# 1-Schematic_optical-sensor.net
KiCad netlist of a schematic drawn in EasyEDA
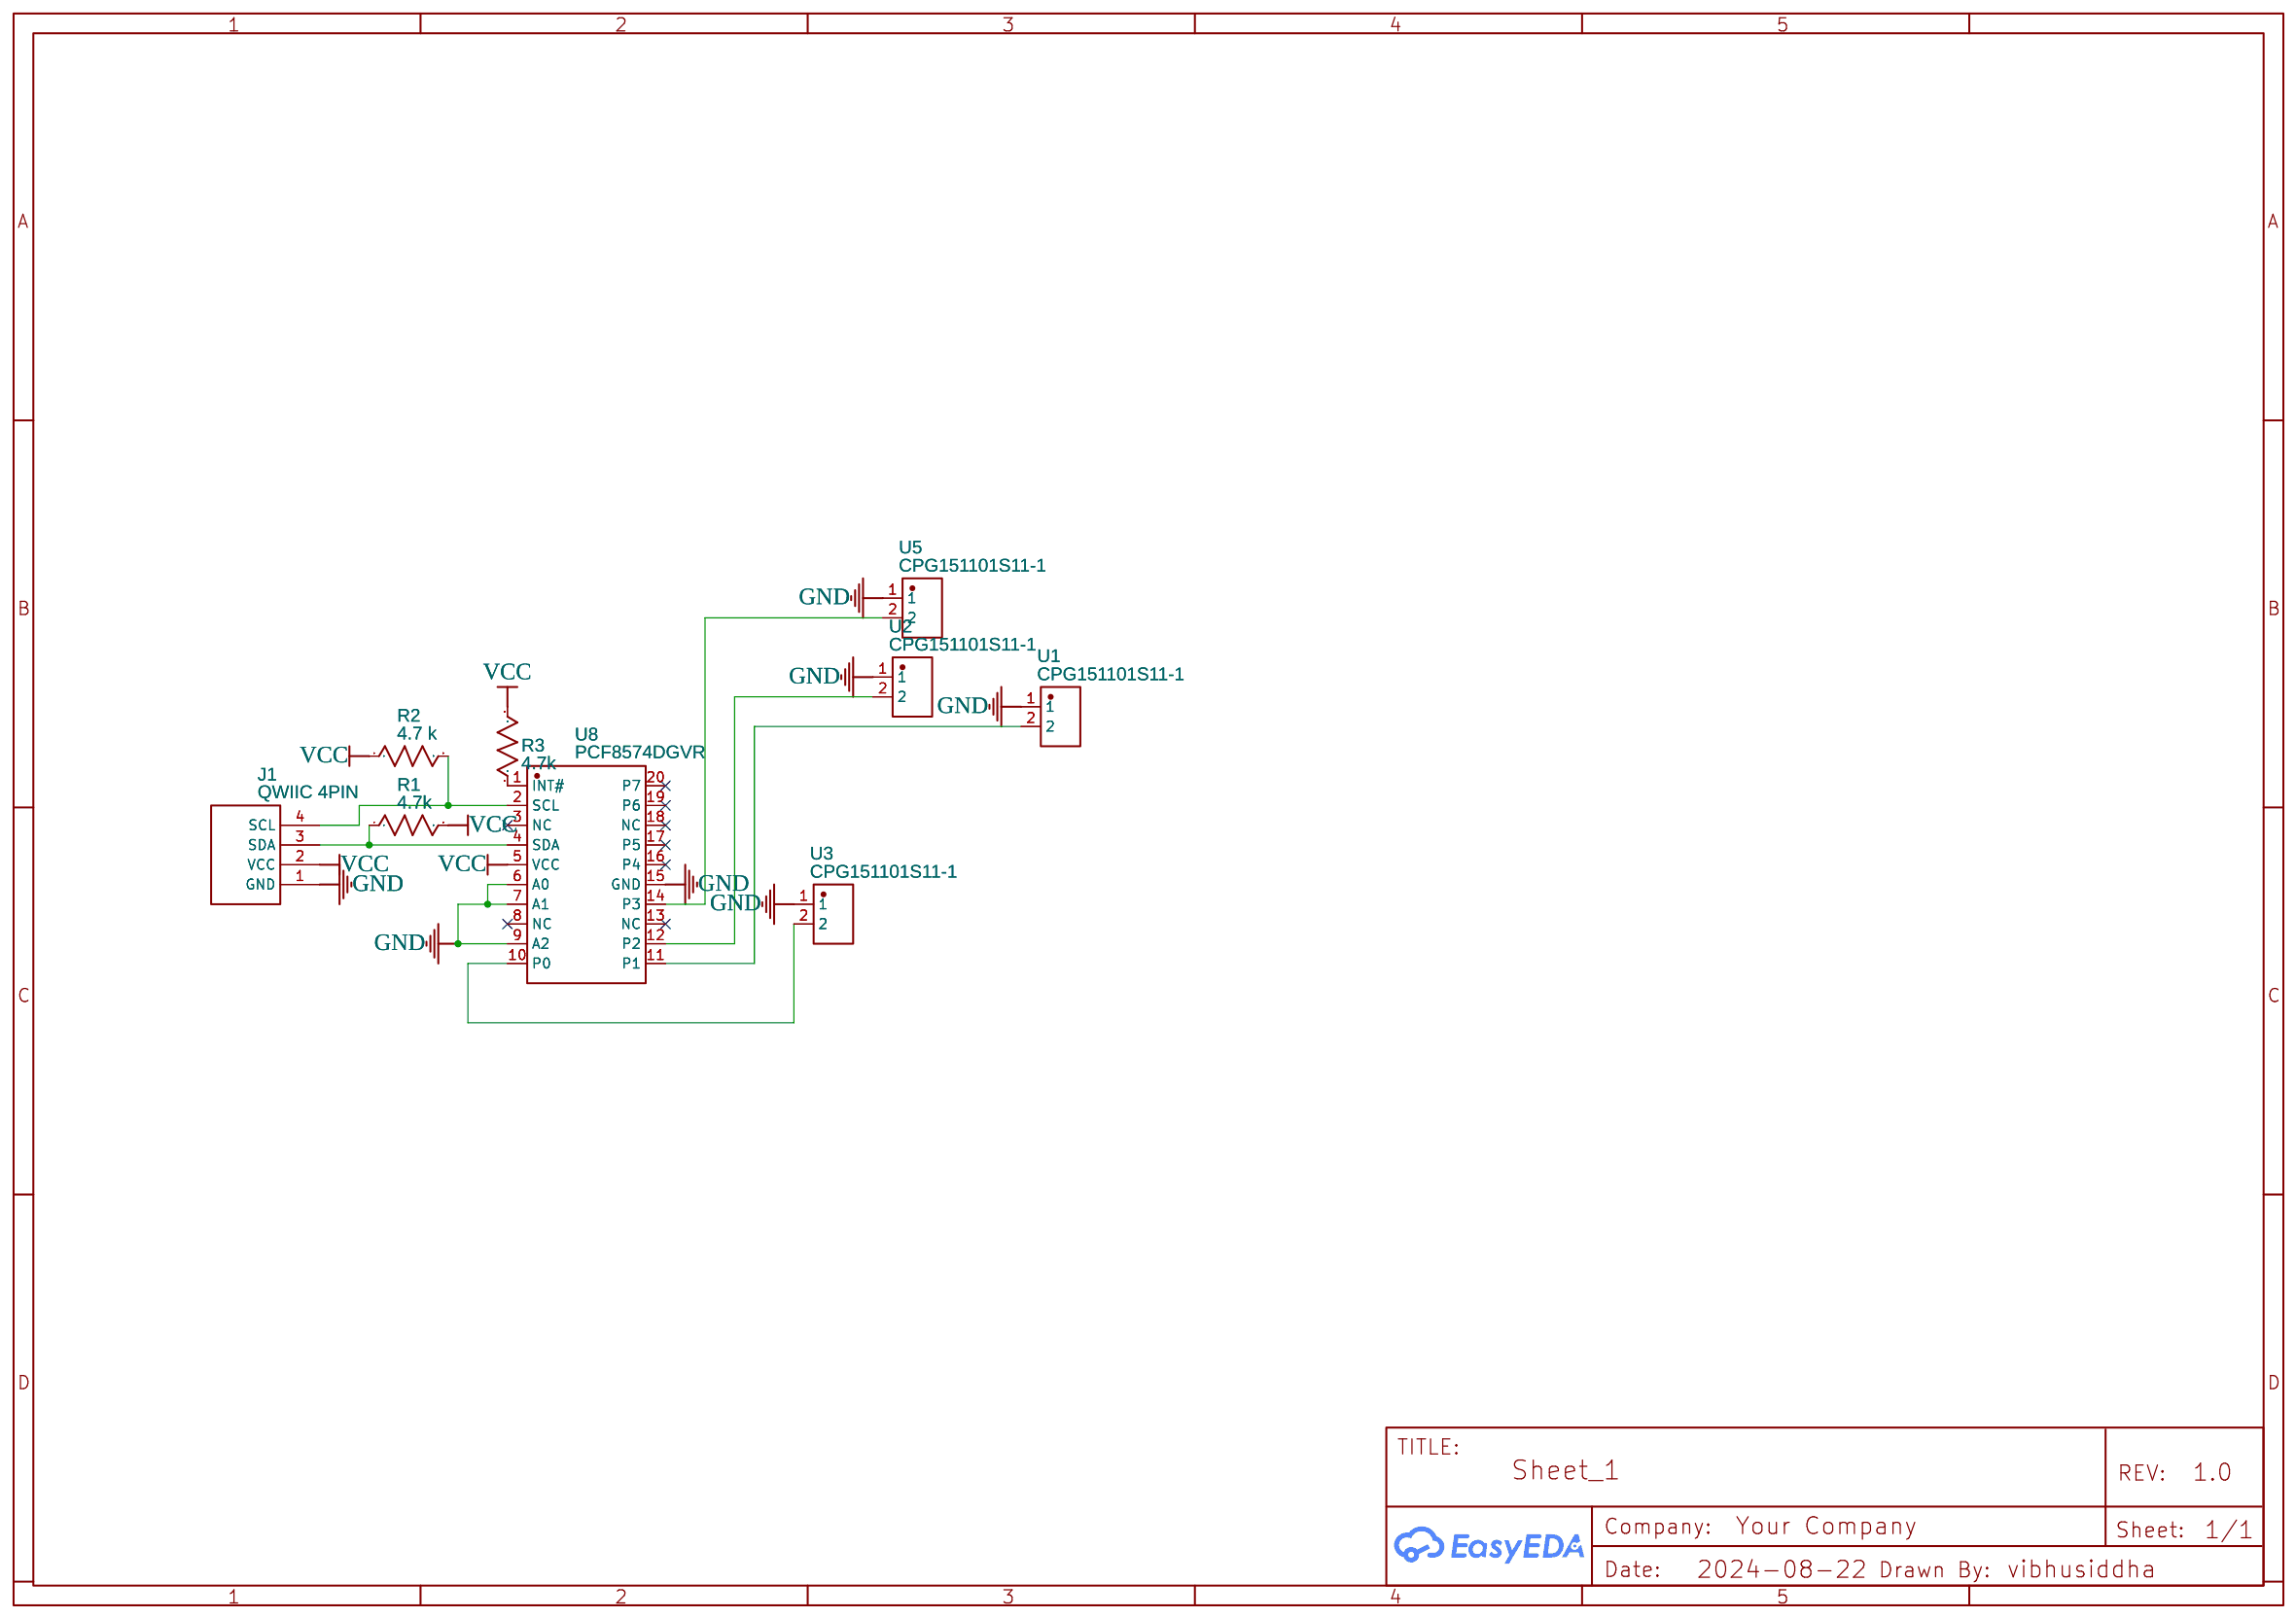
[diagram p0: schematic sheet]

(export (version "E")
  (design (tool "Eeschema 10.0.6"))
  (components
    (comp (ref "J1")
      (value "QWIIC 4PIN")
      (fields
        (field (name "Manufacturer Part") "PRT-14417")
        (field (name "Manufacturer") "SparkFun Electronics")
      )
      (libsource (lib "") (part "QWIIC 4PIN"))
    )
    (comp (ref "R1") (value "4.7k") (libsource (lib "") (part "R_0603_US")))
    (comp (ref "R2") (value "4.7 k") (libsource (lib "") (part "R_0603_US")))
    (comp (ref "R3") (value "4.7k") (libsource (lib "") (part "R_0603_US_1")))
    (comp (ref "U1")
      (value "CPG151101S11-1")
      (fields (field (name "Manufacturer") "Kailh(凯华)"))
      (libsource (lib "") (part "CPG151101S11-1"))
    )
    (comp (ref "U2")
      (value "CPG151101S11-1")
      (fields (field (name "Manufacturer") "Kailh(凯华)"))
      (libsource (lib "") (part "CPG151101S11-1"))
    )
    (comp (ref "U3")
      (value "CPG151101S11-1")
      (fields (field (name "Manufacturer") "Kailh(凯华)"))
      (libsource (lib "") (part "CPG151101S11-1"))
    )
    (comp (ref "U5")
      (value "CPG151101S11-1")
      (fields (field (name "Manufacturer") "Kailh(凯华)"))
      (libsource (lib "") (part "CPG151101S11-1"))
    )
    (comp (ref "U8")
      (value "PCF8574DGVR")
      (fields (field (name "Manufacturer") "TI(德州仪器)"))
      (libsource (lib "") (part "PCF8574DGVR"))
    )
  )
  (nets
    (net (code "1") (name "GND") (class "Default")
      (node (ref "J1") (pin "1") (pinfunction "GND_1") (pintype "unspecified"))
      (node (ref "U1") (pin "1") (pinfunction "1_1") (pintype "unspecified"))
      (node (ref "U2") (pin "1") (pinfunction "1_1") (pintype "unspecified"))
      (node (ref "U3") (pin "1") (pinfunction "1_1") (pintype "unspecified"))
      (node (ref "U5") (pin "1") (pinfunction "1_1") (pintype "unspecified"))
      (node (ref "U8") (pin "15") (pinfunction "GND_15") (pintype "unspecified"))
      (node (ref "U8") (pin "6") (pinfunction "A0_6") (pintype "unspecified"))
      (node (ref "U8") (pin "7") (pinfunction "A1_7") (pintype "unspecified"))
      (node (ref "U8") (pin "9") (pinfunction "A2_9") (pintype "unspecified"))
    )
    (net (code "2") (name "Net-(J1-SCL)") (class "Default")
      (node (ref "J1") (pin "4") (pinfunction "SCL_4") (pintype "unspecified"))
      (node (ref "R2") (pin "2") (pinfunction "2_2") (pintype "unspecified"))
      (node (ref "U8") (pin "2") (pinfunction "SCL_2") (pintype "unspecified"))
    )
    (net (code "3") (name "Net-(J1-SDA)") (class "Default")
      (node (ref "J1") (pin "3") (pinfunction "SDA_3") (pintype "unspecified"))
      (node (ref "R1") (pin "1") (pinfunction "1_1") (pintype "unspecified"))
      (node (ref "U8") (pin "4") (pinfunction "SDA_4") (pintype "unspecified"))
    )
    (net (code "4") (name "Net-(U8-INT#)") (class "Default")
      (node (ref "R3") (pin "1") (pinfunction "1_1") (pintype "unspecified"))
      (node (ref "U8") (pin "1") (pinfunction "INT#_1") (pintype "unspecified"))
    )
    (net (code "5") (name "Net-(U8-P0)") (class "Default")
      (node (ref "U3") (pin "2") (pinfunction "2_2") (pintype "unspecified"))
      (node (ref "U8") (pin "10") (pinfunction "P0_10") (pintype "unspecified"))
    )
    (net (code "6") (name "Net-(U8-P1)") (class "Default")
      (node (ref "U1") (pin "2") (pinfunction "2_2") (pintype "unspecified"))
      (node (ref "U8") (pin "11") (pinfunction "P1_11") (pintype "unspecified"))
    )
    (net (code "7") (name "Net-(U8-P2)") (class "Default")
      (node (ref "U2") (pin "2") (pinfunction "2_2") (pintype "unspecified"))
      (node (ref "U8") (pin "12") (pinfunction "P2_12") (pintype "unspecified"))
    )
    (net (code "8") (name "Net-(U8-P3)") (class "Default")
      (node (ref "U5") (pin "2") (pinfunction "2_2") (pintype "unspecified"))
      (node (ref "U8") (pin "14") (pinfunction "P3_14") (pintype "unspecified"))
    )
    (net (code "9") (name "VCC") (class "Default")
      (node (ref "J1") (pin "2") (pinfunction "VCC_2") (pintype "unspecified"))
      (node (ref "R1") (pin "2") (pinfunction "2_2") (pintype "unspecified"))
      (node (ref "R2") (pin "1") (pinfunction "1_1") (pintype "unspecified"))
      (node (ref "R3") (pin "2") (pinfunction "2_2") (pintype "unspecified"))
      (node (ref "U8") (pin "5") (pinfunction "VCC_5") (pintype "unspecified"))
    )
    (net (code "10") (name "unconnected-(U8-NC-Pad3)") (class "Default")
      (node (ref "U8") (pin "3") (pinfunction "NC_3") (pintype "unspecified+no_connect"))
    )
    (net (code "11") (name "unconnected-(U8-NC-Pad8)") (class "Default")
      (node (ref "U8") (pin "8") (pinfunction "NC_8") (pintype "unspecified+no_connect"))
    )
    (net (code "12") (name "unconnected-(U8-NC-Pad13)") (class "Default")
      (node (ref "U8") (pin "13") (pinfunction "NC_13") (pintype "unspecified+no_connect"))
    )
    (net (code "13") (name "unconnected-(U8-NC-Pad18)") (class "Default")
      (node (ref "U8") (pin "18") (pinfunction "NC_18") (pintype "unspecified+no_connect"))
    )
    (net (code "14") (name "unconnected-(U8-P4-Pad16)") (class "Default")
      (node (ref "U8") (pin "16") (pinfunction "P4_16") (pintype "unspecified+no_connect"))
    )
    (net (code "15") (name "unconnected-(U8-P5-Pad17)") (class "Default")
      (node (ref "U8") (pin "17") (pinfunction "P5_17") (pintype "unspecified+no_connect"))
    )
    (net (code "16") (name "unconnected-(U8-P6-Pad19)") (class "Default")
      (node (ref "U8") (pin "19") (pinfunction "P6_19") (pintype "unspecified+no_connect"))
    )
    (net (code "17") (name "unconnected-(U8-P7-Pad20)") (class "Default")
      (node (ref "U8") (pin "20") (pinfunction "P7_20") (pintype "unspecified+no_connect"))
    )
  )
)
